# fleischerTowR3.net
KiCad netlist of a schematic drawn in Altium Designer
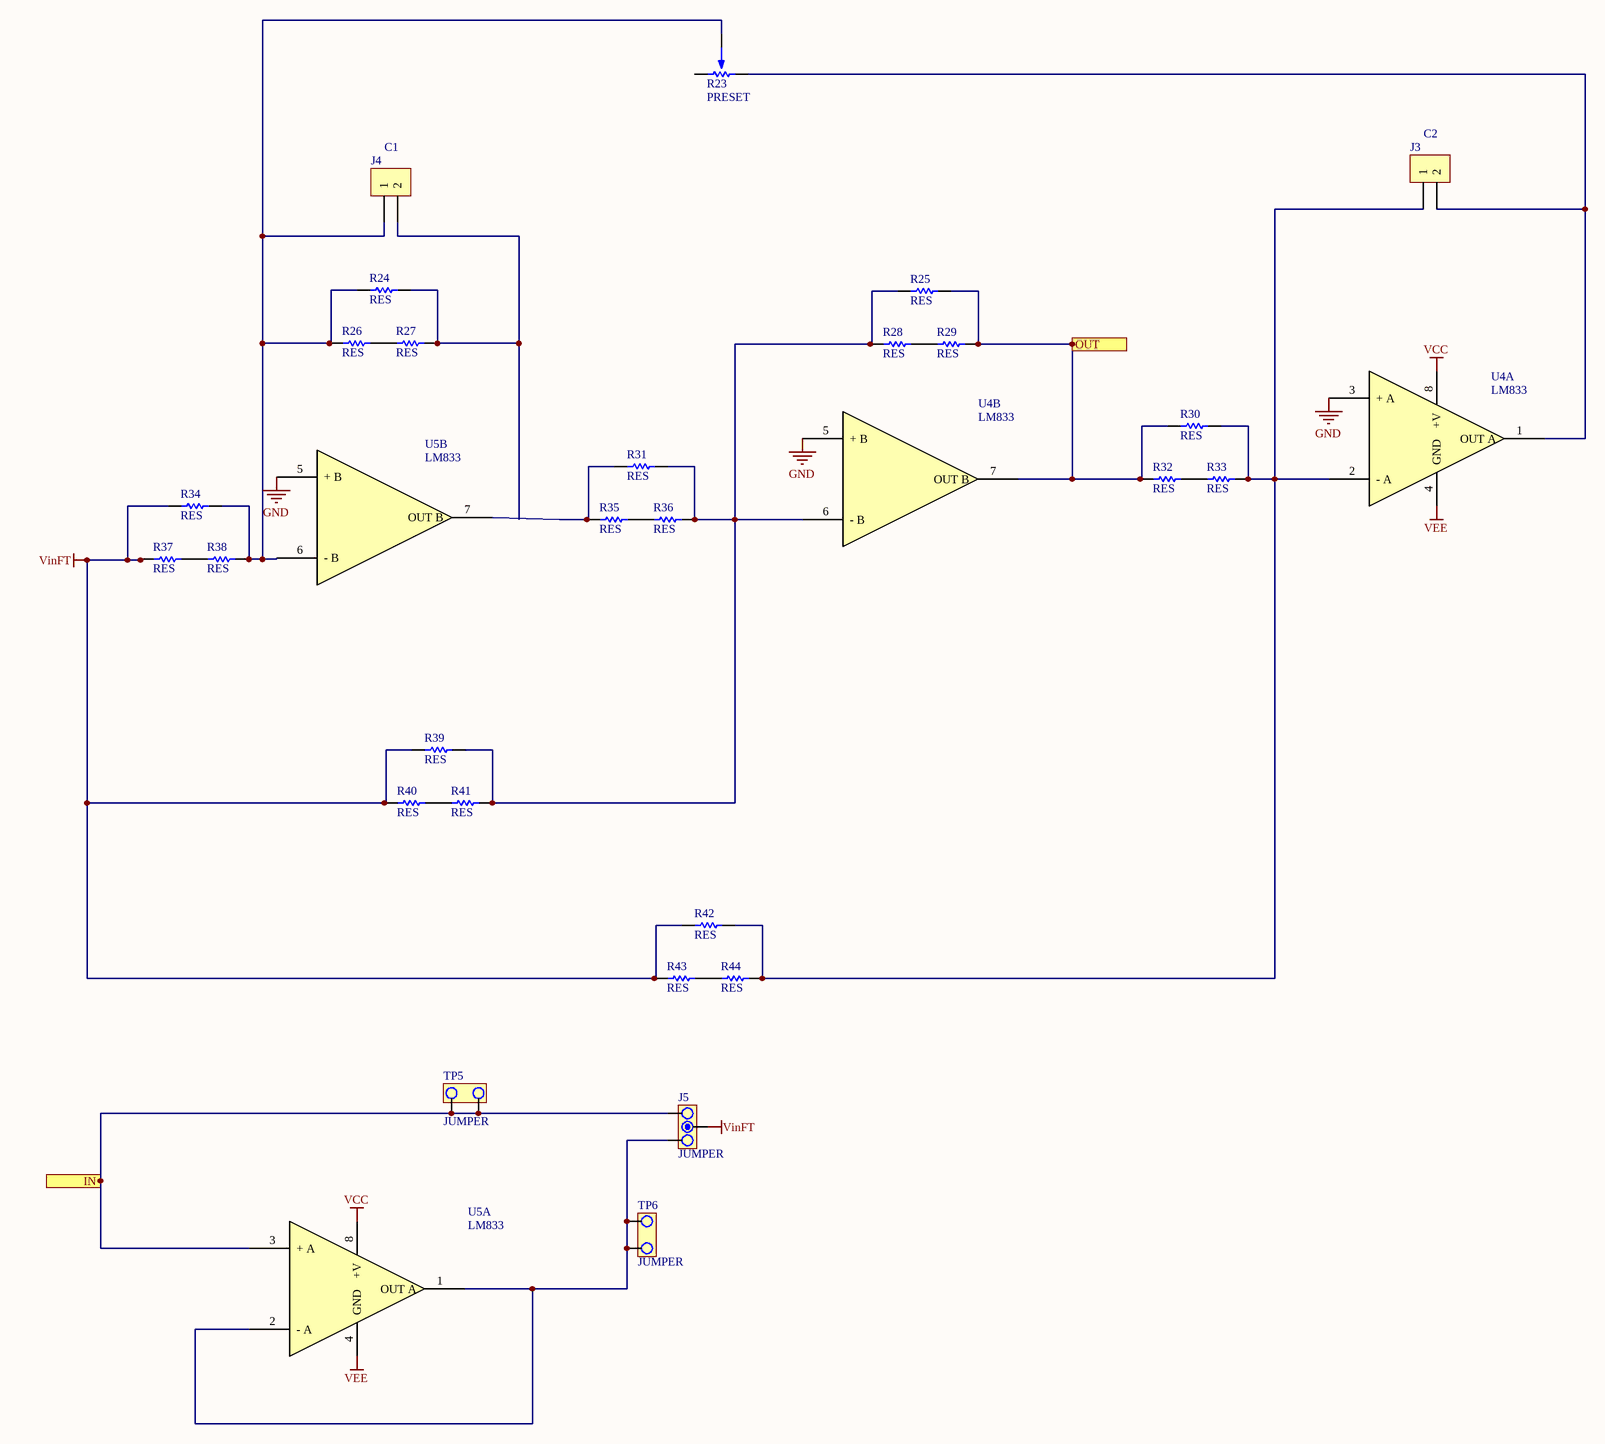
[diagram p0: fleischerTowR3.SchDoc]

(export (version "E")
  (design (tool "Eeschema 10.0.6"))
  (components
    (comp (ref "J3") (value "C2") (footprint "SIP2") (libsource (lib "LIBEBAL") (part "CON2")))
    (comp (ref "J4") (value "C1") (footprint "SIP2") (libsource (lib "LIBEBAL") (part "CON2")))
    (comp (ref "J5") (value "JUMPER") (footprint "JUMPER3") (libsource (lib "LIBEBAL") (part "JUMPER3")))
    (comp (ref "R23") (value "PRESET") (footprint "PRESET H") (libsource (lib "LIBEBAL") (part "PRESET")))
    (comp (ref "R24") (value "RES") (footprint "0805") (libsource (lib "LIBEBAL") (part "RES")))
    (comp (ref "R25") (value "RES") (footprint "0805") (libsource (lib "LIBEBAL") (part "RES")))
    (comp (ref "R26") (value "RES") (footprint "0805") (libsource (lib "LIBEBAL") (part "RES")))
    (comp (ref "R27") (value "RES") (footprint "0805") (libsource (lib "LIBEBAL") (part "RES")))
    (comp (ref "R28") (value "RES") (footprint "0805") (libsource (lib "LIBEBAL") (part "RES")))
    (comp (ref "R29") (value "RES") (footprint "0805") (libsource (lib "LIBEBAL") (part "RES")))
    (comp (ref "R30") (value "RES") (footprint "0805") (libsource (lib "LIBEBAL") (part "RES")))
    (comp (ref "R31") (value "RES") (footprint "0805") (libsource (lib "LIBEBAL") (part "RES")))
    (comp (ref "R32") (value "RES") (footprint "0805") (libsource (lib "LIBEBAL") (part "RES")))
    (comp (ref "R33") (value "RES") (footprint "0805") (libsource (lib "LIBEBAL") (part "RES")))
    (comp (ref "R34") (value "RES") (footprint "0805") (libsource (lib "LIBEBAL") (part "RES")))
    (comp (ref "R35") (value "RES") (footprint "0805") (libsource (lib "LIBEBAL") (part "RES")))
    (comp (ref "R36") (value "RES") (footprint "0805") (libsource (lib "LIBEBAL") (part "RES")))
    (comp (ref "R37") (value "RES") (footprint "0805") (libsource (lib "LIBEBAL") (part "RES")))
    (comp (ref "R38") (value "RES") (footprint "0805") (libsource (lib "LIBEBAL") (part "RES")))
    (comp (ref "R39") (value "RES") (footprint "0805") (libsource (lib "LIBEBAL") (part "RES")))
    (comp (ref "R40") (value "RES") (footprint "0805") (libsource (lib "LIBEBAL") (part "RES")))
    (comp (ref "R41") (value "RES") (footprint "0805") (libsource (lib "LIBEBAL") (part "RES")))
    (comp (ref "R42") (value "RES") (footprint "0805") (libsource (lib "LIBEBAL") (part "RES")))
    (comp (ref "R43") (value "RES") (footprint "0805") (libsource (lib "LIBEBAL") (part "RES")))
    (comp (ref "R44") (value "RES") (footprint "0805") (libsource (lib "LIBEBAL") (part "RES")))
    (comp (ref "TP5") (value "JUMPER") (footprint "JUMPER2") (libsource (lib "") (part "JUMPER_1")))
    (comp (ref "TP6") (value "JUMPER") (footprint "JUMPER2") (libsource (lib "LIBEBAL") (part "JUMPER")))
    (comp (ref "U4")
      (value "LM833")
      (footprint "DIP8")
      (description "Dual Audio Operational Amplifier")
      (libsource (lib "LIBEBAL") (part "LM833"))
    )
    (comp (ref "U5")
      (value "LM833")
      (footprint "DIP8")
      (description "Dual Audio Operational Amplifier")
      (libsource (lib "LIBEBAL") (part "LM833"))
    )
  )
  (nets
    (net (code "1") (name "/IN") (class "Default")
      (node (ref "J5") (pin "3") (pinfunction "3_3") (pintype "passive"))
      (node (ref "TP5") (pin "1") (pinfunction "1_1") (pintype "passive"))
      (node (ref "TP5") (pin "2") (pinfunction "2_2") (pintype "passive"))
      (node (ref "U5") (pin "3") (pinfunction "+_A_3") (pintype "passive"))
    )
    (net (code "2") (name "/OUT") (class "Default")
      (node (ref "R25") (pin "2") (pinfunction "2_2") (pintype "passive"))
      (node (ref "R29") (pin "2") (pinfunction "2_2") (pintype "passive"))
      (node (ref "R30") (pin "1") (pinfunction "1_1") (pintype "passive"))
      (node (ref "R32") (pin "1") (pinfunction "1_1") (pintype "passive"))
      (node (ref "U4") (pin "7") (pinfunction "OUT_B_7") (pintype "passive"))
    )
    (net (code "3") (name "GND") (class "Default")
      (node (ref "U4") (pin "3") (pinfunction "+_A_3") (pintype "passive"))
      (node (ref "U4") (pin "5") (pinfunction "+_B_5") (pintype "passive"))
      (node (ref "U5") (pin "5") (pinfunction "+_B_5") (pintype "passive"))
    )
    (net (code "4") (name "Net-(J4-Pad2)") (class "Default")
      (node (ref "J4") (pin "2") (pinfunction "2_2") (pintype "passive"))
      (node (ref "R24") (pin "2") (pinfunction "2_2") (pintype "passive"))
      (node (ref "R27") (pin "2") (pinfunction "2_2") (pintype "passive"))
    )
    (net (code "5") (name "Net-(R26-Pad2)") (class "Default")
      (node (ref "R26") (pin "2") (pinfunction "2_2") (pintype "passive"))
      (node (ref "R27") (pin "1") (pinfunction "1_1") (pintype "passive"))
    )
    (net (code "6") (name "Net-(R28-Pad2)") (class "Default")
      (node (ref "R28") (pin "2") (pinfunction "2_2") (pintype "passive"))
      (node (ref "R29") (pin "1") (pinfunction "1_1") (pintype "passive"))
    )
    (net (code "7") (name "Net-(R32-Pad2)") (class "Default")
      (node (ref "R32") (pin "2") (pinfunction "2_2") (pintype "passive"))
      (node (ref "R33") (pin "1") (pinfunction "1_1") (pintype "passive"))
    )
    (net (code "8") (name "Net-(R35-Pad2)") (class "Default")
      (node (ref "R35") (pin "2") (pinfunction "2_2") (pintype "passive"))
      (node (ref "R36") (pin "1") (pinfunction "1_1") (pintype "passive"))
    )
    (net (code "9") (name "Net-(R37-Pad2)") (class "Default")
      (node (ref "R37") (pin "2") (pinfunction "2_2") (pintype "passive"))
      (node (ref "R38") (pin "1") (pinfunction "1_1") (pintype "passive"))
    )
    (net (code "10") (name "Net-(R40-Pad2)") (class "Default")
      (node (ref "R40") (pin "2") (pinfunction "2_2") (pintype "passive"))
      (node (ref "R41") (pin "1") (pinfunction "1_1") (pintype "passive"))
    )
    (net (code "11") (name "Net-(R43-Pad2)") (class "Default")
      (node (ref "R43") (pin "2") (pinfunction "2_2") (pintype "passive"))
      (node (ref "R44") (pin "1") (pinfunction "1_1") (pintype "passive"))
    )
    (net (code "12") (name "Net-(U4A--_A)") (class "Default")
      (node (ref "J3") (pin "1") (pinfunction "1_1") (pintype "passive"))
      (node (ref "R30") (pin "2") (pinfunction "2_2") (pintype "passive"))
      (node (ref "R33") (pin "2") (pinfunction "2_2") (pintype "passive"))
      (node (ref "R42") (pin "2") (pinfunction "2_2") (pintype "passive"))
      (node (ref "R44") (pin "2") (pinfunction "2_2") (pintype "passive"))
      (node (ref "U4") (pin "2") (pinfunction "-_A_2") (pintype "passive"))
    )
    (net (code "13") (name "Net-(U4A-OUT_A)") (class "Default")
      (node (ref "J3") (pin "2") (pinfunction "2_2") (pintype "passive"))
      (node (ref "R23") (pin "3") (pinfunction "3_3") (pintype "passive"))
      (node (ref "U4") (pin "1") (pinfunction "OUT_A_1") (pintype "passive"))
    )
    (net (code "14") (name "Net-(U4B--_B)") (class "Default")
      (node (ref "R25") (pin "1") (pinfunction "1_1") (pintype "passive"))
      (node (ref "R28") (pin "1") (pinfunction "1_1") (pintype "passive"))
      (node (ref "R31") (pin "2") (pinfunction "2_2") (pintype "passive"))
      (node (ref "R36") (pin "2") (pinfunction "2_2") (pintype "passive"))
      (node (ref "R39") (pin "2") (pinfunction "2_2") (pintype "passive"))
      (node (ref "R41") (pin "2") (pinfunction "2_2") (pintype "passive"))
      (node (ref "U4") (pin "6") (pinfunction "-_B_6") (pintype "passive"))
    )
    (net (code "15") (name "Net-(U5A--_A)") (class "Default")
      (node (ref "J5") (pin "1") (pinfunction "1_1") (pintype "passive"))
      (node (ref "TP6") (pin "1") (pinfunction "1_1") (pintype "passive"))
      (node (ref "TP6") (pin "2") (pinfunction "2_2") (pintype "passive"))
      (node (ref "U5") (pin "1") (pinfunction "OUT_A_1") (pintype "passive"))
      (node (ref "U5") (pin "2") (pinfunction "-_A_2") (pintype "passive"))
    )
    (net (code "16") (name "Net-(U5B--_B)") (class "Default")
      (node (ref "J4") (pin "1") (pinfunction "1_1") (pintype "passive"))
      (node (ref "R23") (pin "2") (pinfunction "2_2") (pintype "passive"))
      (node (ref "R24") (pin "1") (pinfunction "1_1") (pintype "passive"))
      (node (ref "R26") (pin "1") (pinfunction "1_1") (pintype "passive"))
      (node (ref "R34") (pin "2") (pinfunction "2_2") (pintype "passive"))
      (node (ref "R38") (pin "2") (pinfunction "2_2") (pintype "passive"))
      (node (ref "U5") (pin "6") (pinfunction "-_B_6") (pintype "passive"))
    )
    (net (code "17") (name "Net-(U5B-OUT_B)") (class "Default")
      (node (ref "R31") (pin "1") (pinfunction "1_1") (pintype "passive"))
      (node (ref "R35") (pin "1") (pinfunction "1_1") (pintype "passive"))
      (node (ref "U5") (pin "7") (pinfunction "OUT_B_7") (pintype "passive"))
    )
    (net (code "18") (name "VCC") (class "Default")
      (node (ref "U4") (pin "8") (pinfunction "+V_8") (pintype "passive"))
      (node (ref "U5") (pin "8") (pinfunction "+V_8") (pintype "passive"))
    )
    (net (code "19") (name "VEE") (class "Default")
      (node (ref "U4") (pin "4") (pinfunction "GND_4") (pintype "passive"))
      (node (ref "U5") (pin "4") (pinfunction "GND_4") (pintype "passive"))
    )
    (net (code "20") (name "VinFT") (class "Default")
      (node (ref "J5") (pin "2") (pinfunction "2_2") (pintype "passive"))
      (node (ref "R34") (pin "1") (pinfunction "1_1") (pintype "passive"))
      (node (ref "R37") (pin "1") (pinfunction "1_1") (pintype "passive"))
      (node (ref "R39") (pin "1") (pinfunction "1_1") (pintype "passive"))
      (node (ref "R40") (pin "1") (pinfunction "1_1") (pintype "passive"))
      (node (ref "R42") (pin "1") (pinfunction "1_1") (pintype "passive"))
      (node (ref "R43") (pin "1") (pinfunction "1_1") (pintype "passive"))
    )
    (net (code "21") (name "unconnected-(R23-Pad1)") (class "Default")
      (node (ref "R23") (pin "1") (pinfunction "1_1") (pintype "passive"))
    )
  )
)
